# Step_Down.net
KiCad netlist of a schematic drawn in Altium Designer
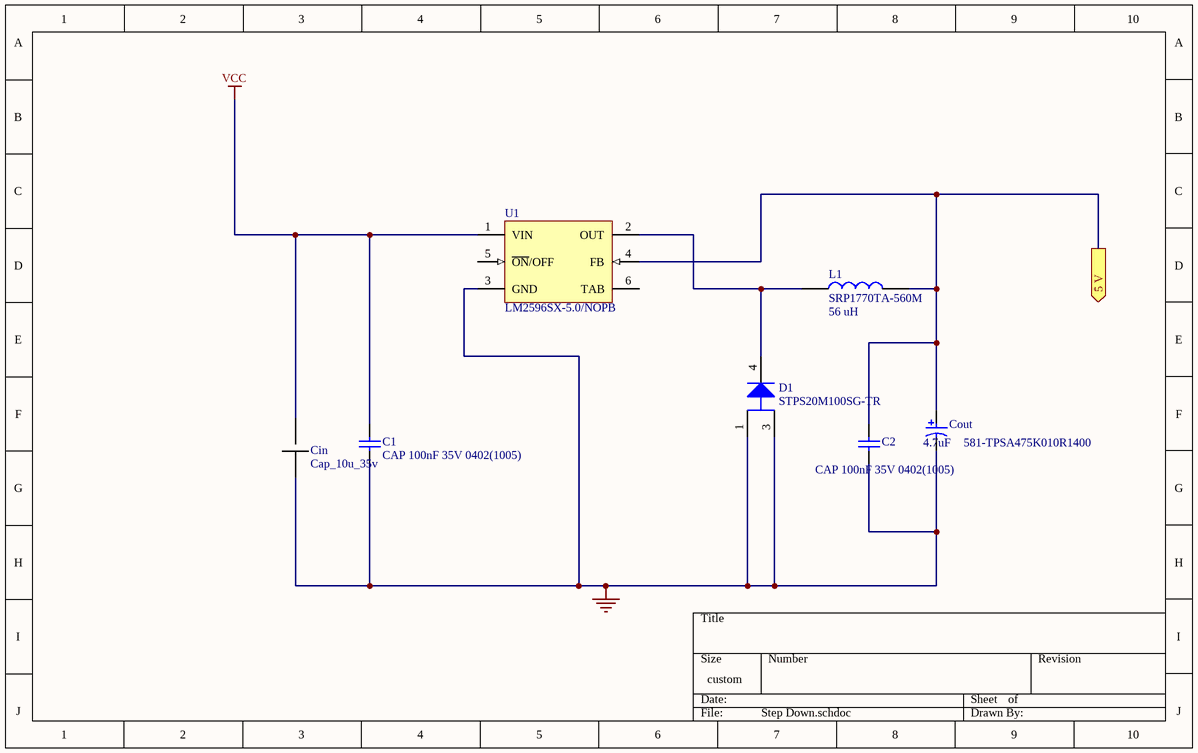
[diagram p0: Step Down.schdoc]

(export (version "E")
  (design (tool "Eeschema 10.0.6"))
  (components
    (comp (ref "C1")
      (value "CAP 100nF 35V 0402(1005)")
      (footprint "CAPC0402(1005)60_N")
      (fields (field (name "TOLERANCE") "Â±20%"))
      (libsource (lib "CAP 0402 100nF 35V") (part "CMP-1034-02076-1"))
    )
    (comp (ref "C2")
      (value "CAP 100nF 35V 0402(1005)")
      (footprint "CAPC0402(1005)60_N")
      (fields (field (name "TOLERANCE") "Â±20%"))
      (libsource (lib "CAP 0402 100nF 35V") (part "CMP-1034-02076-1"))
    )
    (comp (ref "Cin")
      (value "Cap_10u_35v")
      (footprint "Passives:CAP POL 2917/7343")
      (description "80-T491D106M35AT7280")
      (libsource (lib "LibSanhaço2017") (part "Cap_10u_35v"))
    )
    (comp (ref "Cout")
      (value "581-TPSA475K010R1400")
      (footprint "AVX-TAJ-A-2_L")
      (fields
        (field (name "TOLERANCE") "10%")
        (field (name "VOLTAGE") "10V")
        (field (name "MANUFACTURER") "AVX")
        (field (name "CAPACITANCIA") "4.7uF")
      )
      (libsource (lib "CAP 1206 4.7 uF 10V") (part "CMP-2100-03687-1"))
    )
    (comp (ref "D1")
      (value "STPS20M100SG-TR")
      (footprint "ONSC-D2PAK-3-418B-04_J_V")
      (description "SWITCHMODE(TM) Power Rectifier ORing Function Diode, 3-Pin D2PAK, Tape and Reel")
      (fields (field (name "MANUFACTURER") "On Semiconductor"))
      (libsource (lib "Diodo D2PAK") (part "CMP-1055-00080-1"))
    )
    (comp (ref "L1")
      (value "SRP1770TA-560M")
      (footprint "INDPM173169X700N:INDPM173169X700N")
      (fields (field (name "RS PART NUMBER") "9054781") (field (name "INDUTANCIA") "56 uH"))
      (libsource (lib "SRP1770TA-560M") (part "SRP1770TA-560M"))
    )
    (comp (ref "U1")
      (value "LM2596SX-5.0/NOPB")
      (footprint "TS5B_M")
      (description "SIMPLE SWITCHER® Power Converter 150 KHz 3A Step-Down Voltage Regulator, 5-pin TO-263")
      (fields (field (name "MANUFACTURER") "Texas Instruments"))
      (libsource (lib "LM2596SX-5.0") (part "CMP-0069-00282-2"))
    )
  )
  (nets
    (net (code "1") (name "/5 V") (class "Default")
      (node (ref "C2") (pin "2") (pinfunction "2_2") (pintype "passive"))
      (node (ref "Cout") (pin "1") (pinfunction "1_1") (pintype "passive"))
      (node (ref "L1") (pin "2") (pinfunction "2_2") (pintype "passive"))
      (node (ref "U1") (pin "4") (pinfunction "FB_4") (pintype "input"))
    )
    (net (code "2") (name "0") (class "Default")
      (node (ref "C1") (pin "1") (pinfunction "1_1") (pintype "passive"))
      (node (ref "C2") (pin "1") (pinfunction "1_1") (pintype "passive"))
      (node (ref "Cin") (pin "1") (pinfunction "1_1") (pintype "passive"))
      (node (ref "Cout") (pin "2") (pinfunction "2_2") (pintype "passive"))
      (node (ref "D1") (pin "1") (pinfunction "A_1") (pintype "passive"))
      (node (ref "D1") (pin "3") (pinfunction "A_3") (pintype "passive"))
      (node (ref "U1") (pin "3") (pinfunction "GND_3") (pintype "power_in"))
    )
    (net (code "3") (name "Net-(D1-K)") (class "Default")
      (node (ref "D1") (pin "4") (pinfunction "K_4") (pintype "passive"))
      (node (ref "L1") (pin "1") (pinfunction "1_1") (pintype "passive"))
      (node (ref "U1") (pin "2") (pinfunction "OUT_2") (pintype "power_in"))
    )
    (net (code "4") (name "VCC") (class "Default")
      (node (ref "C1") (pin "2") (pinfunction "2_2") (pintype "passive"))
      (node (ref "Cin") (pin "2") (pinfunction "2_2") (pintype "passive"))
      (node (ref "U1") (pin "1") (pinfunction "VIN_1") (pintype "power_in"))
    )
    (net (code "5") (name "unconnected-(U1-TAB-Pad6)") (class "Default")
      (node (ref "U1") (pin "6") (pinfunction "TAB_6") (pintype "power_in"))
    )
    (net (code "6") (name "unconnected-(U1-~{ON}{slash}OFF-Pad5)") (class "Default")
      (node (ref "U1") (pin "5") (pinfunction "~{ON}/OFF_5") (pintype "input"))
    )
  )
)
